# rp_usb_connector.net
KiCad netlist of a schematic drawn in Altium Designer
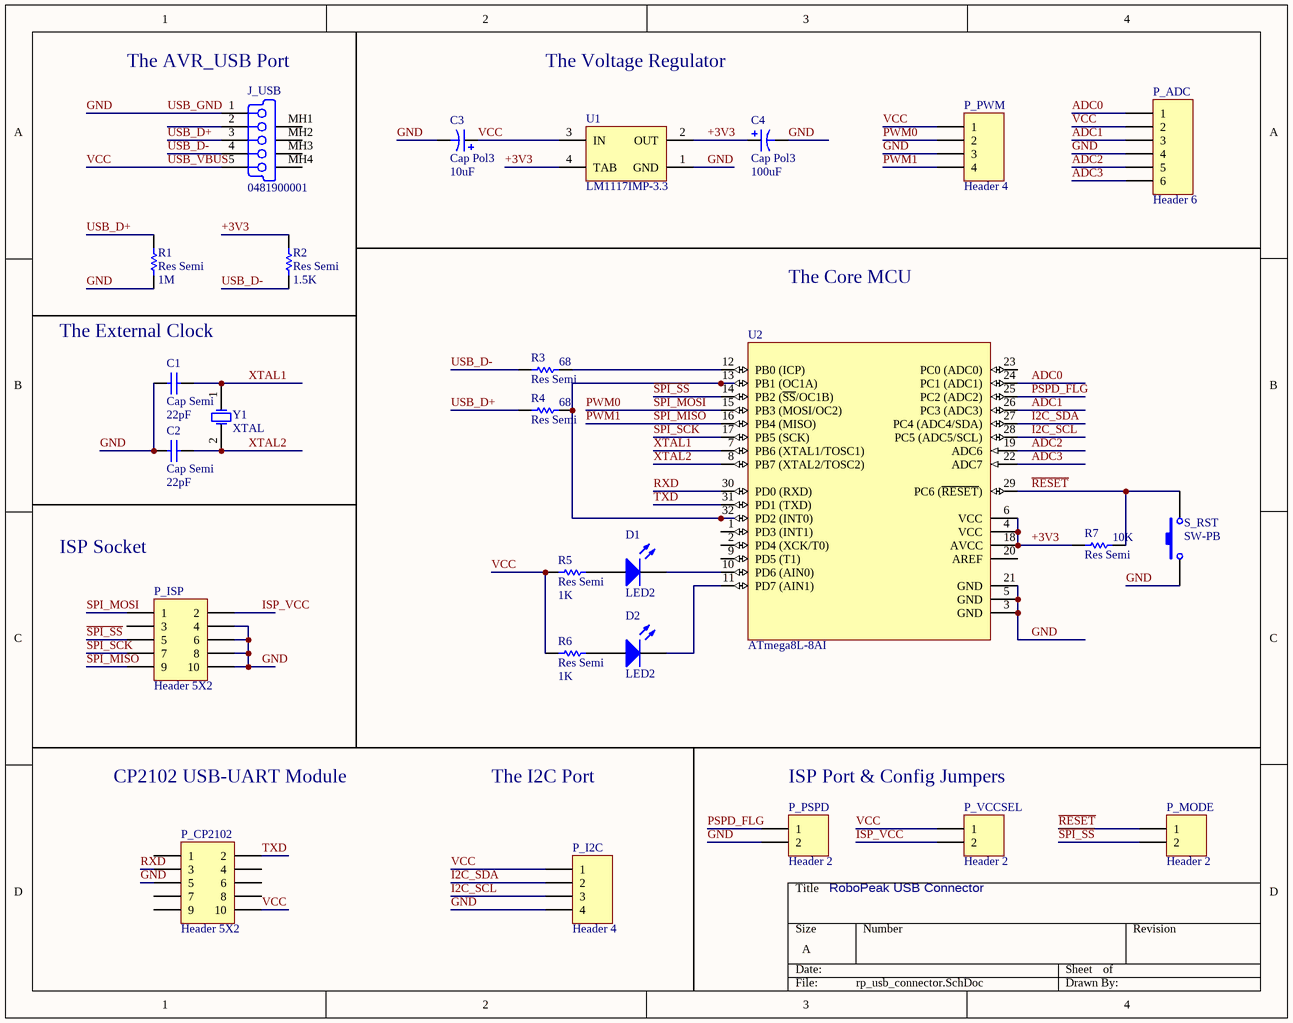
[diagram p0: rp_usb_connector.SchDoc]

(export (version "E")
  (design (tool "Eeschema 10.0.6"))
  (components
    (comp (ref "C1")
      (value "Cap Semi")
      (footprint "C1206")
      (description "Capacitor (Semiconductor SIM Model)")
      (fields (field (name "ALTIUM_VALUE") "22pF") (field (name "PUBLISHER") "Altium Limited"))
      (libsource (lib "Miscellaneous Devices") (part "Cap Semi"))
    )
    (comp (ref "C2")
      (value "Cap Semi")
      (footprint "C1206")
      (description "Capacitor (Semiconductor SIM Model)")
      (fields (field (name "ALTIUM_VALUE") "22pF") (field (name "PUBLISHER") "Altium Limited"))
      (libsource (lib "Miscellaneous Devices") (part "Cap Semi"))
    )
    (comp (ref "C3")
      (value "Cap Pol3")
      (footprint "C3528")
      (description "Polarized Capacitor (Surface Mount)")
      (fields (field (name "ALTIUM_VALUE") "10uF") (field (name "PUBLISHER") "Altium Limited"))
      (libsource (lib "Miscellaneous Devices") (part "Cap Pol3"))
    )
    (comp (ref "C4")
      (value "Cap Pol3")
      (footprint "C3528")
      (description "Polarized Capacitor (Surface Mount)")
      (fields (field (name "ALTIUM_VALUE") "100uF") (field (name "PUBLISHER") "Altium Limited"))
      (libsource (lib "Miscellaneous Devices") (part "Cap Pol3"))
    )
    (comp (ref "D1")
      (value "LED2")
      (footprint "3.2X1.6X1.1")
      (description "Typical RED, GREEN, YELLOW, AMBER GaAs LED")
      (fields (field (name "PUBLISHER") "Altium Limited"))
      (libsource (lib "Miscellaneous Devices") (part "LED2"))
    )
    (comp (ref "D2")
      (value "LED2")
      (footprint "3.2X1.6X1.1")
      (description "Typical RED, GREEN, YELLOW, AMBER GaAs LED")
      (fields (field (name "PUBLISHER") "Altium Limited"))
      (libsource (lib "Miscellaneous Devices") (part "LED2"))
    )
    (comp (ref "J_USB")
      (value "0481900001")
      (footprint "481900001")
      (fields (field (name "PUBLISHER") "Altium Limited"))
      (libsource (lib "Molex Serial Bus Mini USB") (part "0481900001"))
    )
    (comp (ref "P_ADC")
      (value "Header 6")
      (footprint "HDR1X6")
      (description "Header, 6-Pin")
      (fields (field (name "PUBLISHER") "Altium Limited"))
      (libsource (lib "Miscellaneous Connectors") (part "Header 6"))
    )
    (comp (ref "P_CP2102")
      (value "Header 5X2")
      (footprint "HDR2X5")
      (description "Header, 5-Pin, Dual row")
      (fields (field (name "PUBLISHER") "Altium Limited"))
      (libsource (lib "Miscellaneous Connectors") (part "Header 5X2"))
    )
    (comp (ref "P_I2C")
      (value "Header 4")
      (footprint "HDR1X4")
      (description "Header, 4-Pin")
      (fields (field (name "PUBLISHER") "Altium Limited"))
      (libsource (lib "Miscellaneous Connectors") (part "Header 4"))
    )
    (comp (ref "P_ISP")
      (value "Header 5X2")
      (footprint "HDR2X5")
      (description "Header, 5-Pin, Dual row")
      (fields (field (name "PUBLISHER") "Altium Limited"))
      (libsource (lib "Miscellaneous Connectors") (part "Header 5X2"))
    )
    (comp (ref "P_MODE")
      (value "Header 2")
      (footprint "HDR1X2")
      (description "Header, 2-Pin")
      (fields (field (name "PUBLISHER") "Altium Limited"))
      (libsource (lib "Miscellaneous Connectors") (part "Header 2"))
    )
    (comp (ref "P_PSPD")
      (value "Header 2")
      (footprint "HDR1X2")
      (description "Header, 2-Pin")
      (fields (field (name "PUBLISHER") "Altium Limited"))
      (libsource (lib "Miscellaneous Connectors") (part "Header 2"))
    )
    (comp (ref "P_PWM")
      (value "Header 4")
      (footprint "HDR1X4")
      (description "Header, 4-Pin")
      (fields (field (name "PUBLISHER") "Altium Limited"))
      (libsource (lib "Miscellaneous Connectors") (part "Header 4"))
    )
    (comp (ref "P_VCCSEL")
      (value "Header 2")
      (footprint "HDR1X2")
      (description "Header, 2-Pin")
      (fields (field (name "PUBLISHER") "Altium Limited"))
      (libsource (lib "Miscellaneous Connectors") (part "Header 2"))
    )
    (comp (ref "R1")
      (value "Res Semi")
      (footprint "2012[0805]")
      (description "Semiconductor Resistor")
      (fields (field (name "ALTIUM_VALUE") "1M") (field (name "PUBLISHER") "Altium Limited"))
      (libsource (lib "Miscellaneous Devices") (part "Res Semi"))
    )
    (comp (ref "R2")
      (value "Res Semi")
      (footprint "2012[0805]")
      (description "Semiconductor Resistor")
      (fields (field (name "ALTIUM_VALUE") "1.5K") (field (name "PUBLISHER") "Altium Limited"))
      (libsource (lib "Miscellaneous Devices") (part "Res Semi"))
    )
    (comp (ref "R3")
      (value "Res Semi")
      (footprint "2012[0805]")
      (description "Semiconductor Resistor")
      (fields (field (name "ALTIUM_VALUE") "68") (field (name "PUBLISHER") "Altium Limited"))
      (libsource (lib "Miscellaneous Devices") (part "Res Semi"))
    )
    (comp (ref "R4")
      (value "Res Semi")
      (footprint "2012[0805]")
      (description "Semiconductor Resistor")
      (fields (field (name "ALTIUM_VALUE") "68") (field (name "PUBLISHER") "Altium Limited"))
      (libsource (lib "Miscellaneous Devices") (part "Res Semi"))
    )
    (comp (ref "R5")
      (value "Res Semi")
      (footprint "2012[0805]")
      (description "Semiconductor Resistor")
      (fields (field (name "ALTIUM_VALUE") "1K") (field (name "PUBLISHER") "Altium Limited"))
      (libsource (lib "Miscellaneous Devices") (part "Res Semi"))
    )
    (comp (ref "R6")
      (value "Res Semi")
      (footprint "2012[0805]")
      (description "Semiconductor Resistor")
      (fields (field (name "ALTIUM_VALUE") "1K") (field (name "PUBLISHER") "Altium Limited"))
      (libsource (lib "Miscellaneous Devices") (part "Res Semi"))
    )
    (comp (ref "R7")
      (value "Res Semi")
      (footprint "2012[0805]")
      (description "Semiconductor Resistor")
      (fields (field (name "ALTIUM_VALUE") "10K") (field (name "PUBLISHER") "Altium Limited"))
      (libsource (lib "Miscellaneous Devices") (part "Res Semi"))
    )
    (comp (ref "S_RST")
      (value "SW-PB")
      (footprint "SWITCH")
      (description "Switch")
      (fields (field (name "PUBLISHER") "Altium Limited"))
      (libsource (lib "Miscellaneous Devices") (part "SW-PB"))
    )
    (comp (ref "U1")
      (value "LM1117IMP-3.3")
      (footprint "MP04A_N")
      (description "800mA Low-Dropout Linear Regulator")
      (fields
        (field (name "MANUFACTURER") "National Semiconductor")
        (field (name "DIGIKEYPARTNUMBER") "LM1117IMP-3.3CT-ND")
        (field (name "PUBLISHER") "Altium Limited")
      )
      (libsource (lib "NSC LDO") (part "LM1117IMP-3.3"))
    )
    (comp (ref "U2")
      (value "ATmega8L-8AI")
      (footprint "32A_N")
      (description "8-Bit AVR Microcontroller with 8K Bytes of In-System Programmable Flash Memory")
      (fields (field (name "PUBLISHER") "Altium Limited"))
      (libsource (lib "Atmel Microcontroller 8-Bit AVR") (part "ATmega8L-8AI"))
    )
    (comp (ref "Y1")
      (value "XTAL")
      (footprint "HC-49U")
      (description "Crystal Oscillator")
      (fields (field (name "PUBLISHER") "Altium Limited"))
      (libsource (lib "Miscellaneous Devices") (part "XTAL"))
    )
  )
  (nets
    (net (code "1") (name "/+3V3") (class "Default")
      (node (ref "C4") (pin "1") (pinfunction "1_1") (pintype "passive"))
      (node (ref "R2") (pin "2") (pinfunction "2_2") (pintype "passive"))
      (node (ref "R7") (pin "2") (pinfunction "2_2") (pintype "passive"))
      (node (ref "U1") (pin "2") (pinfunction "OUT_2") (pintype "power_in"))
      (node (ref "U1") (pin "4") (pinfunction "TAB_4") (pintype "power_in"))
      (node (ref "U2") (pin "18") (pinfunction "AVCC_18") (pintype "power_in"))
      (node (ref "U2") (pin "4") (pinfunction "VCC_4") (pintype "power_in"))
      (node (ref "U2") (pin "6") (pinfunction "VCC_6") (pintype "power_in"))
    )
    (net (code "2") (name "/ADC0") (class "Default")
      (node (ref "P_ADC") (pin "1") (pinfunction "1_1") (pintype "passive"))
      (node (ref "U2") (pin "24") (pinfunction "PC1_(ADC1)_24") (pintype "bidirectional"))
    )
    (net (code "3") (name "/ADC1") (class "Default")
      (node (ref "P_ADC") (pin "3") (pinfunction "3_3") (pintype "passive"))
      (node (ref "U2") (pin "26") (pinfunction "PC3_(ADC3)_26") (pintype "bidirectional"))
    )
    (net (code "4") (name "/ADC2") (class "Default")
      (node (ref "P_ADC") (pin "5") (pinfunction "5_5") (pintype "passive"))
      (node (ref "U2") (pin "19") (pinfunction "ADC6_19") (pintype "input"))
    )
    (net (code "5") (name "/ADC3") (class "Default")
      (node (ref "P_ADC") (pin "6") (pinfunction "6_6") (pintype "passive"))
      (node (ref "U2") (pin "22") (pinfunction "ADC7_22") (pintype "input"))
    )
    (net (code "6") (name "/GND") (class "Default")
      (node (ref "C1") (pin "1") (pinfunction "1_1") (pintype "passive"))
      (node (ref "C2") (pin "1") (pinfunction "1_1") (pintype "passive"))
      (node (ref "C3") (pin "2") (pinfunction "2_2") (pintype "passive"))
      (node (ref "C4") (pin "2") (pinfunction "2_2") (pintype "passive"))
      (node (ref "J_USB") (pin "1") (pinfunction "V_BUS_(5V)_1") (pintype "passive"))
      (node (ref "P_ADC") (pin "4") (pinfunction "4_4") (pintype "passive"))
      (node (ref "P_CP2102") (pin "5") (pinfunction "5_5") (pintype "passive"))
      (node (ref "P_I2C") (pin "4") (pinfunction "4_4") (pintype "passive"))
      (node (ref "P_ISP") (pin "10") (pinfunction "10_10") (pintype "passive"))
      (node (ref "P_ISP") (pin "4") (pinfunction "4_4") (pintype "passive"))
      (node (ref "P_ISP") (pin "6") (pinfunction "6_6") (pintype "passive"))
      (node (ref "P_ISP") (pin "8") (pinfunction "8_8") (pintype "passive"))
      (node (ref "P_PSPD") (pin "2") (pinfunction "2_2") (pintype "passive"))
      (node (ref "P_PWM") (pin "3") (pinfunction "3_3") (pintype "passive"))
      (node (ref "R1") (pin "1") (pinfunction "1_1") (pintype "passive"))
      (node (ref "S_RST") (pin "1") (pinfunction "1_1") (pintype "passive"))
      (node (ref "U1") (pin "1") (pinfunction "GND_1") (pintype "power_in"))
      (node (ref "U2") (pin "21") (pinfunction "GND_21") (pintype "power_in"))
      (node (ref "U2") (pin "3") (pinfunction "GND_3") (pintype "power_in"))
      (node (ref "U2") (pin "5") (pinfunction "GND_5") (pintype "power_in"))
    )
    (net (code "7") (name "/I2C_SCL") (class "Default")
      (node (ref "P_I2C") (pin "3") (pinfunction "3_3") (pintype "passive"))
      (node (ref "U2") (pin "28") (pinfunction "PC5_(ADC5/SCL)_28") (pintype "bidirectional"))
    )
    (net (code "8") (name "/I2C_SDA") (class "Default")
      (node (ref "P_I2C") (pin "2") (pinfunction "2_2") (pintype "passive"))
      (node (ref "U2") (pin "27") (pinfunction "PC4_(ADC4/SDA)_27") (pintype "bidirectional"))
    )
    (net (code "9") (name "/ISP_VCC") (class "Default")
      (node (ref "P_ISP") (pin "2") (pinfunction "2_2") (pintype "passive"))
      (node (ref "P_VCCSEL") (pin "2") (pinfunction "2_2") (pintype "passive"))
    )
    (net (code "10") (name "/PSPD_FLG") (class "Default")
      (node (ref "P_PSPD") (pin "1") (pinfunction "1_1") (pintype "passive"))
      (node (ref "U2") (pin "25") (pinfunction "PC2_(ADC2)_25") (pintype "bidirectional"))
    )
    (net (code "11") (name "/PWM0") (class "Default")
      (node (ref "P_ISP") (pin "1") (pinfunction "1_1") (pintype "passive"))
      (node (ref "P_PWM") (pin "2") (pinfunction "2_2") (pintype "passive"))
      (node (ref "U2") (pin "15") (pinfunction "PB3_(MOSI/OC2)_15") (pintype "bidirectional"))
    )
    (net (code "12") (name "/PWM1") (class "Default")
      (node (ref "P_ISP") (pin "9") (pinfunction "9_9") (pintype "passive"))
      (node (ref "P_PWM") (pin "4") (pinfunction "4_4") (pintype "passive"))
      (node (ref "U2") (pin "16") (pinfunction "PB4_(MISO)_16") (pintype "bidirectional"))
    )
    (net (code "13") (name "/RXD") (class "Default")
      (node (ref "P_CP2102") (pin "3") (pinfunction "3_3") (pintype "passive"))
      (node (ref "U2") (pin "30") (pinfunction "PD0_(RXD)_30") (pintype "bidirectional"))
    )
    (net (code "14") (name "/SPI_SCK") (class "Default")
      (node (ref "P_ISP") (pin "7") (pinfunction "7_7") (pintype "passive"))
      (node (ref "U2") (pin "17") (pinfunction "PB5_(SCK)_17") (pintype "bidirectional"))
    )
    (net (code "15") (name "/TXD") (class "Default")
      (node (ref "P_CP2102") (pin "2") (pinfunction "2_2") (pintype "passive"))
      (node (ref "U2") (pin "31") (pinfunction "PD1_(TXD)_31") (pintype "bidirectional"))
    )
    (net (code "16") (name "/USB_D+") (class "Default")
      (node (ref "J_USB") (pin "3") (pinfunction "D+_3") (pintype "passive"))
      (node (ref "R1") (pin "2") (pinfunction "2_2") (pintype "passive"))
      (node (ref "R4") (pin "2") (pinfunction "2_2") (pintype "passive"))
    )
    (net (code "17") (name "/USB_D-") (class "Default")
      (node (ref "J_USB") (pin "4") (pinfunction "NC_4") (pintype "passive"))
      (node (ref "R2") (pin "1") (pinfunction "1_1") (pintype "passive"))
      (node (ref "R3") (pin "2") (pinfunction "2_2") (pintype "passive"))
    )
    (net (code "18") (name "/USB_VBUS") (class "Default")
      (node (ref "C3") (pin "1") (pinfunction "1_1") (pintype "passive"))
      (node (ref "J_USB") (pin "5") (pinfunction "GND_5") (pintype "passive"))
      (node (ref "P_ADC") (pin "2") (pinfunction "2_2") (pintype "passive"))
      (node (ref "P_CP2102") (pin "10") (pinfunction "10_10") (pintype "passive"))
      (node (ref "P_I2C") (pin "1") (pinfunction "1_1") (pintype "passive"))
      (node (ref "P_PWM") (pin "1") (pinfunction "1_1") (pintype "passive"))
      (node (ref "P_VCCSEL") (pin "1") (pinfunction "1_1") (pintype "passive"))
      (node (ref "R5") (pin "1") (pinfunction "1_1") (pintype "passive"))
      (node (ref "R6") (pin "1") (pinfunction "1_1") (pintype "passive"))
      (node (ref "U1") (pin "3") (pinfunction "IN_3") (pintype "power_in"))
    )
    (net (code "19") (name "/XTAL1") (class "Default")
      (node (ref "C1") (pin "2") (pinfunction "2_2") (pintype "passive"))
      (node (ref "U2") (pin "7") (pinfunction "PB6_(XTAL1/TOSC1)_7") (pintype "bidirectional"))
      (node (ref "Y1") (pin "1") (pinfunction "OSC1_1") (pintype "passive"))
    )
    (net (code "20") (name "/XTAL2") (class "Default")
      (node (ref "C2") (pin "2") (pinfunction "2_2") (pintype "passive"))
      (node (ref "U2") (pin "8") (pinfunction "PB7_(XTAL2/TOSC2)_8") (pintype "bidirectional"))
      (node (ref "Y1") (pin "2") (pinfunction "OSC2_2") (pintype "passive"))
    )
    (net (code "21") (name "/~{RESET}") (class "Default")
      (node (ref "P_MODE") (pin "1") (pinfunction "1_1") (pintype "passive"))
      (node (ref "R7") (pin "1") (pinfunction "1_1") (pintype "passive"))
      (node (ref "S_RST") (pin "2") (pinfunction "2_2") (pintype "passive"))
      (node (ref "U2") (pin "29") (pinfunction "PC6_(~{RESET})_29") (pintype "bidirectional"))
    )
    (net (code "22") (name "/~{SPI_SS}") (class "Default")
      (node (ref "P_ISP") (pin "5") (pinfunction "5_5") (pintype "passive"))
      (node (ref "P_MODE") (pin "2") (pinfunction "2_2") (pintype "passive"))
      (node (ref "U2") (pin "14") (pinfunction "PB2_(~{SS}/OC1B)_14") (pintype "bidirectional"))
    )
    (net (code "23") (name "Net-(D1-A)") (class "Default")
      (node (ref "D1") (pin "1") (pinfunction "A_1") (pintype "passive"))
      (node (ref "R5") (pin "2") (pinfunction "2_2") (pintype "passive"))
    )
    (net (code "24") (name "Net-(D1-K)") (class "Default")
      (node (ref "D1") (pin "2") (pinfunction "K_2") (pintype "passive"))
      (node (ref "U2") (pin "10") (pinfunction "PD6_(AIN0)_10") (pintype "bidirectional"))
    )
    (net (code "25") (name "Net-(D2-A)") (class "Default")
      (node (ref "D2") (pin "1") (pinfunction "A_1") (pintype "passive"))
      (node (ref "R6") (pin "2") (pinfunction "2_2") (pintype "passive"))
    )
    (net (code "26") (name "Net-(D2-K)") (class "Default")
      (node (ref "D2") (pin "2") (pinfunction "K_2") (pintype "passive"))
      (node (ref "U2") (pin "11") (pinfunction "PD7_(AIN1)_11") (pintype "bidirectional"))
    )
    (net (code "27") (name "Net-(U2-PB0_(ICP))") (class "Default")
      (node (ref "R3") (pin "1") (pinfunction "1_1") (pintype "passive"))
      (node (ref "U2") (pin "12") (pinfunction "PB0_(ICP)_12") (pintype "bidirectional"))
    )
    (net (code "28") (name "Net-(U2-PB1_(OC1A))") (class "Default")
      (node (ref "R4") (pin "1") (pinfunction "1_1") (pintype "passive"))
      (node (ref "U2") (pin "13") (pinfunction "PB1_(OC1A)_13") (pintype "bidirectional"))
      (node (ref "U2") (pin "32") (pinfunction "PD2_(INT0)_32") (pintype "bidirectional"))
    )
    (net (code "29") (name "unconnected-(J_USB-D--Pad2)") (class "Default")
      (node (ref "J_USB") (pin "2") (pinfunction "D-_2") (pintype "passive"))
    )
    (net (code "30") (name "unconnected-(J_USB-Tab-PadMH1)") (class "Default")
      (node (ref "J_USB") (pin "MH1") (pinfunction "Tab_MH1") (pintype "passive"))
    )
    (net (code "31") (name "unconnected-(J_USB-Tab-PadMH2)") (class "Default")
      (node (ref "J_USB") (pin "MH2") (pinfunction "Tab_MH2") (pintype "passive"))
    )
    (net (code "32") (name "unconnected-(J_USB-Tab-PadMH3)") (class "Default")
      (node (ref "J_USB") (pin "MH3") (pinfunction "Tab_MH3") (pintype "passive"))
    )
    (net (code "33") (name "unconnected-(J_USB-Tab-PadMH4)") (class "Default")
      (node (ref "J_USB") (pin "MH4") (pinfunction "Tab_MH4") (pintype "passive"))
    )
    (net (code "34") (name "unconnected-(P_CP2102-Pad1)") (class "Default")
      (node (ref "P_CP2102") (pin "1") (pinfunction "1_1") (pintype "passive"))
    )
    (net (code "35") (name "unconnected-(P_CP2102-Pad4)") (class "Default")
      (node (ref "P_CP2102") (pin "4") (pinfunction "4_4") (pintype "passive"))
    )
    (net (code "36") (name "unconnected-(P_CP2102-Pad6)") (class "Default")
      (node (ref "P_CP2102") (pin "6") (pinfunction "6_6") (pintype "passive"))
    )
    (net (code "37") (name "unconnected-(P_CP2102-Pad7)") (class "Default")
      (node (ref "P_CP2102") (pin "7") (pinfunction "7_7") (pintype "passive"))
    )
    (net (code "38") (name "unconnected-(P_CP2102-Pad8)") (class "Default")
      (node (ref "P_CP2102") (pin "8") (pinfunction "8_8") (pintype "passive"))
    )
    (net (code "39") (name "unconnected-(P_CP2102-Pad9)") (class "Default")
      (node (ref "P_CP2102") (pin "9") (pinfunction "9_9") (pintype "passive"))
    )
    (net (code "40") (name "unconnected-(P_ISP-Pad3)") (class "Default")
      (node (ref "P_ISP") (pin "3") (pinfunction "3_3") (pintype "passive"))
    )
    (net (code "41") (name "unconnected-(U2-AREF-Pad20)") (class "Default")
      (node (ref "U2") (pin "20") (pinfunction "AREF_20") (pintype "passive"))
    )
    (net (code "42") (name "unconnected-(U2-PC0_(ADC0)-Pad23)") (class "Default")
      (node (ref "U2") (pin "23") (pinfunction "PC0_(ADC0)_23") (pintype "bidirectional"))
    )
    (net (code "43") (name "unconnected-(U2-PD3_(INT1)-Pad1)") (class "Default")
      (node (ref "U2") (pin "1") (pinfunction "PD3_(INT1)_1") (pintype "bidirectional"))
    )
    (net (code "44") (name "unconnected-(U2-PD4_(XCK{slash}T0)-Pad2)") (class "Default")
      (node (ref "U2") (pin "2") (pinfunction "PD4_(XCK/T0)_2") (pintype "bidirectional"))
    )
    (net (code "45") (name "unconnected-(U2-PD5_(T1)-Pad9)") (class "Default")
      (node (ref "U2") (pin "9") (pinfunction "PD5_(T1)_9") (pintype "bidirectional"))
    )
  )
)
